# PCBA-2075-01.net
KiCad netlist of a schematic drawn in Altium Designer
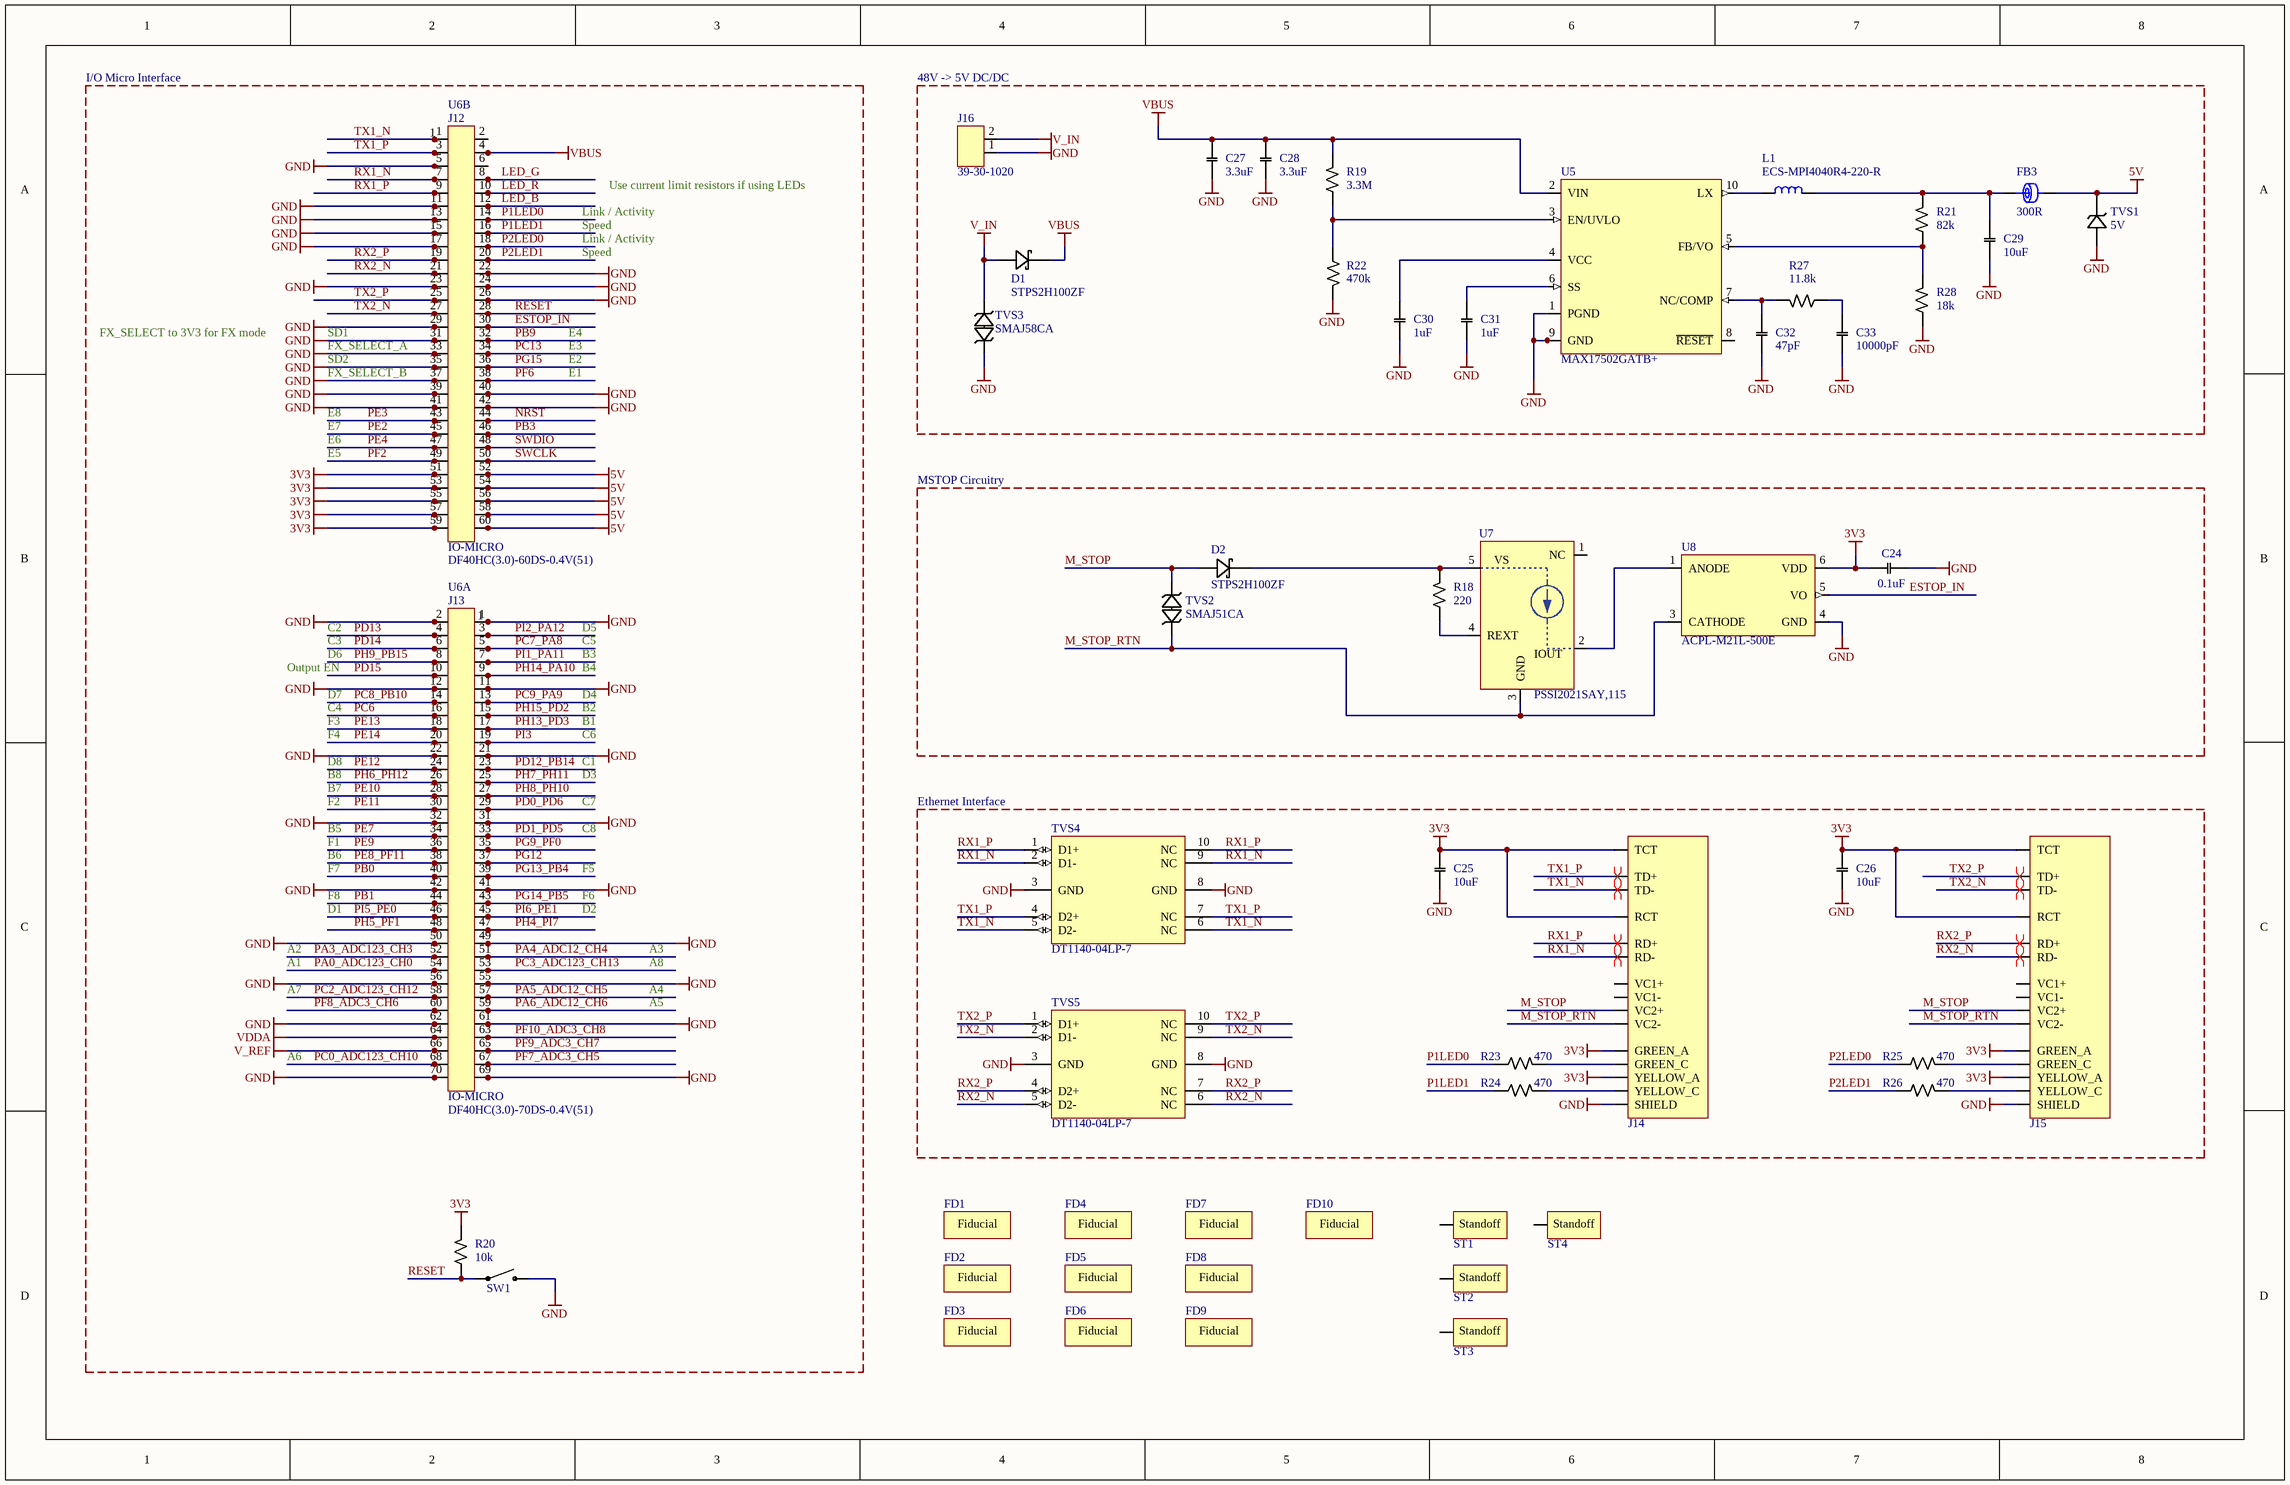
[diagram p0: PCBA-2075-01.SchDoc]

(export (version "E")
  (design (tool "Eeschema 10.0.6"))
  (components
    (comp (ref "C24")
      (value "C-0.1uf-X7R-25V-10%-0402")
      (footprint "C0402")
      (description "Capacitor Ceramic 0.1uF 25V X7R 10% SMD 0402")
      (fields (field (name "TOLERANCE") "10%") (field (name "CAPACITANCE") "0.1uF"))
      (libsource (lib "Hebi Robotics") (part "Capacitor"))
    )
    (comp (ref "C25")
      (value "C-10uf-X5R-25V-10%-0805")
      (footprint "C0805")
      (description "Capacitor Ceramic 10uF 25V X5R 10% SMD 0805")
      (fields (field (name "TOLERANCE") "10%") (field (name "CAPACITANCE") "10uF"))
      (libsource (lib "Hebi Robotics") (part "Capacitor"))
    )
    (comp (ref "C26")
      (value "C-10uf-X5R-25V-10%-0805")
      (footprint "C0805")
      (description "Capacitor Ceramic 10uF 25V X5R 10% SMD 0805")
      (fields (field (name "TOLERANCE") "10%") (field (name "CAPACITANCE") "10uF"))
      (libsource (lib "Hebi Robotics") (part "Capacitor"))
    )
    (comp (ref "C27")
      (value "C-3.3uf-X7S-100V-10%-1206")
      (footprint "C1206")
      (description "Capacitor Ceramic 3.3uF 100V X7S 10% SMD 1206")
      (fields (field (name "TOLERANCE") "±10%") (field (name "CAPACITANCE") "3.3uF"))
      (libsource (lib "Hebi Robotics") (part "Capacitor"))
    )
    (comp (ref "C28")
      (value "C-3.3uf-X7S-100V-10%-1206")
      (footprint "C1206")
      (description "Capacitor Ceramic 3.3uF 100V X7S 10% SMD 1206")
      (fields (field (name "TOLERANCE") "±10%") (field (name "CAPACITANCE") "3.3uF"))
      (libsource (lib "Hebi Robotics") (part "Capacitor"))
    )
    (comp (ref "C29")
      (value "C-10uf-X5R-16V-10%-0603")
      (footprint "C0603")
      (description "Capacitor Ceramic 10uF 16V X5R 10% SMD 0603")
      (fields (field (name "TOLERANCE") "10%") (field (name "CAPACITANCE") "10uF"))
      (libsource (lib "Hebi Robotics") (part "Capacitor"))
    )
    (comp (ref "C30")
      (value "C-1uf-X5R-25V-10%-0402")
      (footprint "C0402")
      (description "Capacitor Ceramic 1uF 25V X5R 10% SMD 0402")
      (fields (field (name "TOLERANCE") "±10%") (field (name "CAPACITANCE") "1uF"))
      (libsource (lib "Hebi Robotics") (part "Capacitor"))
    )
    (comp (ref "C31")
      (value "C-1uf-X5R-25V-10%-0402")
      (footprint "C0402")
      (description "Capacitor Ceramic 1uF 25V X5R 10% SMD 0402")
      (fields (field (name "TOLERANCE") "±10%") (field (name "CAPACITANCE") "1uF"))
      (libsource (lib "Hebi Robotics") (part "Capacitor"))
    )
    (comp (ref "C32")
      (value "C-47pf-C0G-NP0-50V-5%-0402")
      (footprint "C0402")
      (description "Capacitor Ceramic 47pF 50V C0G, NP0 5% SMD 0402")
      (fields (field (name "CAPACITANCE") "47pF") (field (name "TOLERANCE") "±5%"))
      (libsource (lib "Hebi Robotics") (part "Capacitor"))
    )
    (comp (ref "C33")
      (value "C-10000pf-X7R-50V-10%-0402")
      (footprint "C0402")
      (description "Capacitor Ceramic 10000pF 50V X7R 10% SMD 0402")
      (fields (field (name "TOLERANCE") "10%") (field (name "CAPACITANCE") "10000pF"))
      (libsource (lib "Hebi Robotics") (part "Capacitor"))
    )
    (comp (ref "D1")
      (value "STPS2H100ZF")
      (footprint "SOD123F_ST")
      (description "DIODE SCHOTTKY 100V 2A SOD123F")
      (libsource (lib "Hebi Robotics") (part "SCHOTTKY"))
    )
    (comp (ref "D2")
      (value "STPS2H100ZF")
      (footprint "SOD123F_ST")
      (description "DIODE SCHOTTKY 100V 2A SOD123F")
      (libsource (lib "Hebi Robotics") (part "SCHOTTKY"))
    )
    (comp (ref "FB3")
      (value "MI0603L301R-10")
      (footprint "FB0603")
      (description "FERRITE BEAD 300 OHM 0603 2A")
      (fields (field (name "IMPEDANCE") "300R"))
      (libsource (lib "Hebi Robotics") (part "FB"))
    )
    (comp (ref "FD1")
      (value "Fiducial")
      (footprint "New footprint 1")
      (description "Fiducial with Overlay")
      (libsource (lib "Hebi Robotics") (part "FIDUCIAL"))
    )
    (comp (ref "FD2")
      (value "Fiducial")
      (footprint "New footprint 1")
      (description "Fiducial with Overlay")
      (libsource (lib "Hebi Robotics") (part "FIDUCIAL"))
    )
    (comp (ref "FD3")
      (value "Fiducial")
      (footprint "New footprint 1")
      (description "Fiducial with Overlay")
      (libsource (lib "Hebi Robotics") (part "FIDUCIAL"))
    )
    (comp (ref "FD4")
      (value "Fiducial")
      (footprint "New footprint 1")
      (description "Fiducial with Overlay")
      (libsource (lib "Hebi Robotics") (part "FIDUCIAL"))
    )
    (comp (ref "FD5")
      (value "Fiducial No Overlay")
      (footprint "New footprint 1")
      (description "Fiducial without Overlay")
      (libsource (lib "Hebi Robotics") (part "FIDUCIAL"))
    )
    (comp (ref "FD6")
      (value "Fiducial No Overlay")
      (footprint "New footprint 1")
      (description "Fiducial without Overlay")
      (libsource (lib "Hebi Robotics") (part "FIDUCIAL"))
    )
    (comp (ref "FD7")
      (value "Fiducial No Overlay")
      (footprint "New footprint 1")
      (description "Fiducial without Overlay")
      (libsource (lib "Hebi Robotics") (part "FIDUCIAL"))
    )
    (comp (ref "FD8")
      (value "Fiducial No Overlay")
      (footprint "New footprint 1")
      (description "Fiducial without Overlay")
      (libsource (lib "Hebi Robotics") (part "FIDUCIAL"))
    )
    (comp (ref "FD9")
      (value "Fiducial No Overlay")
      (footprint "New footprint 1")
      (description "Fiducial without Overlay")
      (libsource (lib "Hebi Robotics") (part "FIDUCIAL"))
    )
    (comp (ref "FD10")
      (value "Fiducial No Overlay")
      (footprint "New footprint 1")
      (description "Fiducial without Overlay")
      (libsource (lib "Hebi Robotics") (part "FIDUCIAL"))
    )
    (comp (ref "J12")
      (value "DF40HC(3.0)-60DS-0.4V(51)")
      (footprint "DF40HC(3.0)-60DS-0.4V(51)")
      (description "CONN RCPT 60POS 0.4MM SMD GOLD")
      (libsource (lib "Hebi Robotics") (part "CONN_2_ROW_060_POS"))
    )
    (comp (ref "J13")
      (value "DF40HC(3.0)-70DS-0.4V(51)")
      (footprint "DF40HC(3.0)-70DS-0.4V(51)")
      (description "CONN RCPT 70POS 0.4MM SMD GOLD")
      (fields (field (name "MANUFACTURER") "Hirose"))
      (libsource (lib "Hebi Robotics") (part "CONN_2_ROW_070_POS"))
    )
    (comp (ref "J14")
      (value "ARJM11C7-114-BA-EW2")
      (footprint "ARJM11C7-114-BA-EW2-Footprint-1")
      (description "1 Port RJ45 Magjack Connector Through Hole 10/100 Base-T, AutoMDIX, Power over Ethernet (PoE)")
      (libsource (lib "Hebi Robotics") (part "ARJM11C7-114-BA-EW2"))
    )
    (comp (ref "J15")
      (value "ARJM11C7-114-BA-EW2")
      (footprint "ARJM11C7-114-BA-EW2-Footprint-1")
      (description "1 Port RJ45 Magjack Connector Through Hole 10/100 Base-T, AutoMDIX, Power over Ethernet (PoE)")
      (libsource (lib "Hebi Robotics") (part "ARJM11C7-114-BA-EW2"))
    )
    (comp (ref "J16")
      (value "39-30-1020")
      (footprint "39-30-1020")
      (description "CONN HEADER 2POS 4.2MM R/A TIN")
      (fields (field (name "MANUFACTURER") "Molex Inc"))
      (libsource (lib "Hebi Robotics") (part "CONN_1_ROW_002_POS"))
    )
    (comp (ref "L1")
      (value "ECS-MPI4040R4-220-R")
      (footprint "MPI4040R4")
      (description "FIXED IND 22UH 1.3A 316 MOHM SMD")
      (fields (field (name "TOLERANCE") "±20%"))
      (libsource (lib "Hebi Robotics") (part "Inductor"))
    )
    (comp (ref "R18")
      (value "R-220-1%-0.25w-0603")
      (footprint "R0603")
      (description "Resistor 0603 220 Ohm 1% 1-4 Watt")
      (fields (field (name "POWER") "0.25W, 1/4W") (field (name "RESISTANCE") "220"))
      (libsource (lib "Hebi Robotics") (part "Resistor"))
    )
    (comp (ref "R19")
      (value "R-3.3m-1%-0.063w-0402")
      (footprint "R0402")
      (description "Resistor 0402 3.3m Ohm 1% 1-16 Watt")
      (fields (field (name "POWER") "0.063W, 1/16W") (field (name "RESISTANCE") "3.3M"))
      (libsource (lib "Hebi Robotics") (part "Resistor"))
    )
    (comp (ref "R20")
      (value "R-10k-1%-0.063w-0402")
      (footprint "R0402")
      (description "Resistor 0402 10k Ohm 1% 1-16 Watt")
      (fields
        (field (name "POWER") "0.063W, 1/16W")
        (field (name "RESISTANCE") "10k")
        (field (name "TOLERANCE") "1%")
      )
      (libsource (lib "Hebi Robotics") (part "Resistor"))
    )
    (comp (ref "R21")
      (value "R-82k-1%-0.063w-0402")
      (footprint "R0402")
      (description "Resistor 0402 82k Ohm 1% 1-16 Watt")
      (fields (field (name "POWER") "0.063W, 1/16W") (field (name "RESISTANCE") "82k"))
      (libsource (lib "Hebi Robotics") (part "Resistor"))
    )
    (comp (ref "R22")
      (value "R-470k-1%-0.063w-0402")
      (footprint "R0402")
      (description "Resistor 0402 470k Ohm 1% 1-16 Watt")
      (fields
        (field (name "POWER") "0.063W, 1/16W")
        (field (name "RESISTANCE") "470k")
        (field (name "TOLERANCE") "1%")
      )
      (libsource (lib "Hebi Robotics") (part "Resistor"))
    )
    (comp (ref "R23")
      (value "R-470-1%-0.063w-0402")
      (footprint "R0402")
      (description "Resistor 0402 470 Ohm 1% 1-16 Watt")
      (fields
        (field (name "POWER") "0.063W, 1/16W")
        (field (name "RESISTANCE") "470")
        (field (name "TOLERANCE") "1%")
      )
      (libsource (lib "Hebi Robotics") (part "Resistor"))
    )
    (comp (ref "R24")
      (value "R-470-1%-0.063w-0402")
      (footprint "R0402")
      (description "Resistor 0402 470 Ohm 1% 1-16 Watt")
      (fields
        (field (name "POWER") "0.063W, 1/16W")
        (field (name "RESISTANCE") "470")
        (field (name "TOLERANCE") "1%")
      )
      (libsource (lib "Hebi Robotics") (part "Resistor"))
    )
    (comp (ref "R25")
      (value "R-470-1%-0.063w-0402")
      (footprint "R0402")
      (description "Resistor 0402 470 Ohm 1% 1-16 Watt")
      (fields
        (field (name "POWER") "0.063W, 1/16W")
        (field (name "RESISTANCE") "470")
        (field (name "TOLERANCE") "1%")
      )
      (libsource (lib "Hebi Robotics") (part "Resistor"))
    )
    (comp (ref "R26")
      (value "R-470-1%-0.063w-0402")
      (footprint "R0402")
      (description "Resistor 0402 470 Ohm 1% 1-16 Watt")
      (fields
        (field (name "POWER") "0.063W, 1/16W")
        (field (name "RESISTANCE") "470")
        (field (name "TOLERANCE") "1%")
      )
      (libsource (lib "Hebi Robotics") (part "Resistor"))
    )
    (comp (ref "R27")
      (value "R-11.8k-1%-0.063w-0402")
      (footprint "R0402")
      (description "Resistor 0402 11.8k Ohm 1% 1-16 Watt")
      (fields (field (name "POWER") "0.063W, 1/16W") (field (name "RESISTANCE") "11.8k"))
      (libsource (lib "Hebi Robotics") (part "Resistor"))
    )
    (comp (ref "R28")
      (value "R-18k-1%-0.063w-0402")
      (footprint "R0402")
      (description "Resistor 0402 18k Ohm 1% 1-16 Watt")
      (fields
        (field (name "TOLERANCE") "1%")
        (field (name "POWER") "0.063W, 1/16W")
        (field (name "RESISTANCE") "18k")
      )
      (libsource (lib "Hebi Robotics") (part "Resistor"))
    )
    (comp (ref "ST1")
      (value "9774030960R")
      (footprint "9774030960R")
      (description "ROUND SPACER M3.3 STEEL 3MM")
      (fields (field (name "MANUFACTURER") "Wurth Electronics Inc"))
      (libsource (lib "Hebi Robotics") (part "STANDOFF_PIN"))
    )
    (comp (ref "ST2")
      (value "9774030960R")
      (footprint "9774030960R")
      (description "ROUND SPACER M3.3 STEEL 3MM")
      (fields (field (name "MANUFACTURER") "Wurth Electronics Inc"))
      (libsource (lib "Hebi Robotics") (part "STANDOFF_PIN"))
    )
    (comp (ref "ST3")
      (value "9774030960R")
      (footprint "9774030960R")
      (description "ROUND SPACER M3.3 STEEL 3MM")
      (fields (field (name "MANUFACTURER") "Wurth Electronics Inc"))
      (libsource (lib "Hebi Robotics") (part "STANDOFF_PIN"))
    )
    (comp (ref "ST4")
      (value "9774030960R")
      (footprint "9774030960R")
      (description "ROUND SPACER M3.3 STEEL 3MM")
      (fields (field (name "MANUFACTURER") "Wurth Electronics Inc"))
      (libsource (lib "Hebi Robotics") (part "STANDOFF_PIN"))
    )
    (comp (ref "SW1")
      (value "222ADVBA")
      (footprint "222ADVBA")
      (description "Tactile Switch SPST-NO Top Actuated Through Hole")
      (fields (field (name "MANUFACTURER") "CTS"))
      (libsource (lib "Hebi Robotics") (part "SPST_NO"))
    )
    (comp (ref "TVS1")
      (value "PTVS5V0S1UR,115")
      (footprint "SOD-123W_NXP")
      (description "TVS DIODE 5VWM 9.2VC SOD123W")
      (fields (field (name "VOLTAGE - REVERSE STANDOFF (TYP)") "5V"))
      (libsource (lib "Hebi Robotics") (part "TVS"))
    )
    (comp (ref "TVS2")
      (value "SMAJ51CA")
      (footprint "SMA_BI_BOURNS")
      (description "TVS DIODE 51VWM 82.4VC DO214AC")
      (libsource (lib "Hebi Robotics") (part "TVS_BI"))
    )
    (comp (ref "TVS3")
      (value "SMAJ58CA")
      (footprint "SMA_BI_BOURNS")
      (description "TVS DIODE 58VWM 93.6VC SMA")
      (libsource (lib "Hebi Robotics") (part "TVS_BI"))
    )
    (comp (ref "TVS4")
      (value "DT1140-04LP-7")
      (footprint "USON10_TI")
      (description "TVS DIODE 5.5V 10V U-DFN2510-10")
      (libsource (lib "Hebi Robotics") (part "10-UFDFN-TVS"))
    )
    (comp (ref "TVS5")
      (value "DT1140-04LP-7")
      (footprint "USON10_TI")
      (description "TVS DIODE 5.5V 10V U-DFN2510-10")
      (libsource (lib "Hebi Robotics") (part "10-UFDFN-TVS"))
    )
    (comp (ref "U5")
      (value "MAX17502GATB+")
      (footprint "10_TDFN_MAXIM")
      (description "Switching Voltage Regulators 60V 1A 600kHz Synch Step-Down Regulator")
      (libsource (lib "Hebi Robotics") (part "MAX17502E_F_G"))
    )
    (comp (ref "U6")
      (value "IO-MICRO")
      (footprint "IO-MICRO-Footprint-1")
      (description "IO Micro Composite Component")
      (libsource (lib "") (part "IO-MICRO-Symbol-1_1"))
    )
    (comp (ref "U7")
      (value "PSSI2021SAY,115")
      (footprint "PSSI2021SAY,115")
      (description "IC CURRENT SOURCE SOT353")
      (libsource (lib "Hebi Robotics") (part "PSSI2021SAY,115"))
    )
    (comp (ref "U8")
      (value "ACPL-M21L-500E")
      (footprint "SOT125P700X260-5N")
      (description "OPTOISO 3.75KV PUSH PULL 5SO")
      (libsource (lib "Hebi Robotics") (part "Symbol"))
    )
  )
  (nets
    (net (code "1") (name "/ESTOP_IN") (class "Default")
      (node (ref "J12") (pin "30") (pinfunction "30_30") (pintype "passive"))
      (node (ref "U6") (pin "B30") (pinfunction "B30_B30") (pintype "passive"))
      (node (ref "U8") (pin "5") (pinfunction "VO_5") (pintype "output"))
    )
    (net (code "2") (name "/LED_B") (class "Default")
      (node (ref "J12") (pin "12") (pinfunction "12_12") (pintype "passive"))
      (node (ref "U6") (pin "B12") (pinfunction "B12_B12") (pintype "passive"))
    )
    (net (code "3") (name "/LED_G") (class "Default")
      (node (ref "J12") (pin "8") (pinfunction "8_8") (pintype "passive"))
      (node (ref "U6") (pin "B8") (pinfunction "B8_B8") (pintype "passive"))
    )
    (net (code "4") (name "/LED_R") (class "Default")
      (node (ref "J12") (pin "10") (pinfunction "10_10") (pintype "passive"))
      (node (ref "U6") (pin "B10") (pinfunction "B10_B10") (pintype "passive"))
    )
    (net (code "5") (name "/M_STOP") (class "Default")
      (node (ref "D2") (pin "A") (pinfunction "A_A") (pintype "passive"))
      (node (ref "J14") (pin "6") (pinfunction "VC2+_6") (pintype "passive"))
      (node (ref "J15") (pin "6") (pinfunction "VC2+_6") (pintype "passive"))
      (node (ref "TVS2") (pin "C") (pinfunction "C_C") (pintype "passive"))
    )
    (net (code "6") (name "/M_STOP_RTN") (class "Default")
      (node (ref "J14") (pin "1") (pinfunction "VC2-_1") (pintype "passive"))
      (node (ref "J15") (pin "1") (pinfunction "VC2-_1") (pintype "passive"))
      (node (ref "TVS2") (pin "A") (pinfunction "A_A") (pintype "passive"))
      (node (ref "U7") (pin "3") (pinfunction "GND_3") (pintype "passive"))
      (node (ref "U8") (pin "3") (pinfunction "CATHODE_3") (pintype "passive"))
    )
    (net (code "7") (name "/NRST") (class "Default")
      (node (ref "J12") (pin "44") (pinfunction "44_44") (pintype "passive"))
      (node (ref "U6") (pin "B44") (pinfunction "B44_B44") (pintype "passive"))
    )
    (net (code "8") (name "/P1LED0") (class "Default")
      (node (ref "J12") (pin "14") (pinfunction "14_14") (pintype "passive"))
      (node (ref "R23") (pin "1") (pinfunction "1_1") (pintype "passive"))
      (node (ref "U6") (pin "B14") (pinfunction "B14_B14") (pintype "passive"))
    )
    (net (code "9") (name "/P1LED1") (class "Default")
      (node (ref "J12") (pin "16") (pinfunction "16_16") (pintype "passive"))
      (node (ref "R24") (pin "1") (pinfunction "1_1") (pintype "passive"))
      (node (ref "U6") (pin "B16") (pinfunction "B16_B16") (pintype "passive"))
    )
    (net (code "10") (name "/P2LED0") (class "Default")
      (node (ref "J12") (pin "18") (pinfunction "18_18") (pintype "passive"))
      (node (ref "R25") (pin "1") (pinfunction "1_1") (pintype "passive"))
      (node (ref "U6") (pin "B18") (pinfunction "B18_B18") (pintype "passive"))
    )
    (net (code "11") (name "/P2LED1") (class "Default")
      (node (ref "J12") (pin "20") (pinfunction "20_20") (pintype "passive"))
      (node (ref "R26") (pin "1") (pinfunction "1_1") (pintype "passive"))
      (node (ref "U6") (pin "B20") (pinfunction "B20_B20") (pintype "passive"))
    )
    (net (code "12") (name "/PA0_ADC123_CH0") (class "Default")
      (node (ref "J13") (pin "54") (pinfunction "54_54") (pintype "passive"))
      (node (ref "U6") (pin "A54") (pinfunction "A54_A54") (pintype "passive"))
    )
    (net (code "13") (name "/PA3_ADC123_CH3") (class "Default")
      (node (ref "J13") (pin "52") (pinfunction "52_52") (pintype "passive"))
      (node (ref "U6") (pin "A52") (pinfunction "A52_A52") (pintype "passive"))
    )
    (net (code "14") (name "/PA4_ADC12_CH4") (class "Default")
      (node (ref "J13") (pin "51") (pinfunction "51_51") (pintype "passive"))
      (node (ref "U6") (pin "A51") (pinfunction "A51_A51") (pintype "passive"))
    )
    (net (code "15") (name "/PA5_ADC12_CH5") (class "Default")
      (node (ref "J13") (pin "57") (pinfunction "57_57") (pintype "passive"))
      (node (ref "U6") (pin "A57") (pinfunction "A57_A57") (pintype "passive"))
    )
    (net (code "16") (name "/PA6_ADC12_CH6") (class "Default")
      (node (ref "J13") (pin "59") (pinfunction "59_59") (pintype "passive"))
      (node (ref "U6") (pin "A59") (pinfunction "A59_A59") (pintype "passive"))
    )
    (net (code "17") (name "/PB0") (class "Default")
      (node (ref "J13") (pin "40") (pinfunction "40_40") (pintype "passive"))
      (node (ref "U6") (pin "A40") (pinfunction "A40_A40") (pintype "passive"))
    )
    (net (code "18") (name "/PB1") (class "Default")
      (node (ref "J13") (pin "44") (pinfunction "44_44") (pintype "passive"))
      (node (ref "U6") (pin "A44") (pinfunction "A44_A44") (pintype "passive"))
    )
    (net (code "19") (name "/PB3") (class "Default")
      (node (ref "J12") (pin "46") (pinfunction "46_46") (pintype "passive"))
      (node (ref "U6") (pin "B46") (pinfunction "B46_B46") (pintype "passive"))
    )
    (net (code "20") (name "/PB9") (class "Default")
      (node (ref "J12") (pin "32") (pinfunction "32_32") (pintype "passive"))
      (node (ref "U6") (pin "B32") (pinfunction "B32_B32") (pintype "passive"))
    )
    (net (code "21") (name "/PC0_ADC123_CH10") (class "Default")
      (node (ref "J13") (pin "68") (pinfunction "68_68") (pintype "passive"))
      (node (ref "U6") (pin "A68") (pinfunction "A68_A68") (pintype "passive"))
    )
    (net (code "22") (name "/PC2_ADC123_CH12") (class "Default")
      (node (ref "J13") (pin "58") (pinfunction "58_58") (pintype "passive"))
      (node (ref "U6") (pin "A58") (pinfunction "A58_A58") (pintype "passive"))
    )
    (net (code "23") (name "/PC3_ADC123_CH13") (class "Default")
      (node (ref "J13") (pin "53") (pinfunction "53_53") (pintype "passive"))
      (node (ref "U6") (pin "A53") (pinfunction "A53_A53") (pintype "passive"))
    )
    (net (code "24") (name "/PC6") (class "Default")
      (node (ref "J13") (pin "16") (pinfunction "16_16") (pintype "passive"))
      (node (ref "U6") (pin "A16") (pinfunction "A16_A16") (pintype "passive"))
    )
    (net (code "25") (name "/PC7_PA8") (class "Default")
      (node (ref "J13") (pin "5") (pinfunction "5_5") (pintype "passive"))
      (node (ref "U6") (pin "A5") (pinfunction "A5_A5") (pintype "passive"))
    )
    (net (code "26") (name "/PC8_PB10") (class "Default")
      (node (ref "J13") (pin "14") (pinfunction "14_14") (pintype "passive"))
      (node (ref "U6") (pin "A14") (pinfunction "A14_A14") (pintype "passive"))
    )
    (net (code "27") (name "/PC9_PA9") (class "Default")
      (node (ref "J13") (pin "13") (pinfunction "13_13") (pintype "passive"))
      (node (ref "U6") (pin "A13") (pinfunction "A13_A13") (pintype "passive"))
    )
    (net (code "28") (name "/PC13") (class "Default")
      (node (ref "J12") (pin "34") (pinfunction "34_34") (pintype "passive"))
      (node (ref "U6") (pin "B34") (pinfunction "B34_B34") (pintype "passive"))
    )
    (net (code "29") (name "/PD0_PD6") (class "Default")
      (node (ref "J13") (pin "29") (pinfunction "29_29") (pintype "passive"))
      (node (ref "U6") (pin "A29") (pinfunction "A29_A29") (pintype "passive"))
    )
    (net (code "30") (name "/PD1_PD5") (class "Default")
      (node (ref "J13") (pin "33") (pinfunction "33_33") (pintype "passive"))
      (node (ref "U6") (pin "A33") (pinfunction "A33_A33") (pintype "passive"))
    )
    (net (code "31") (name "/PD12_PB14") (class "Default")
      (node (ref "J13") (pin "23") (pinfunction "23_23") (pintype "passive"))
      (node (ref "U6") (pin "A23") (pinfunction "A23_A23") (pintype "passive"))
    )
    (net (code "32") (name "/PD13") (class "Default")
      (node (ref "J13") (pin "4") (pinfunction "4_4") (pintype "passive"))
      (node (ref "U6") (pin "A4") (pinfunction "A4_A4") (pintype "passive"))
    )
    (net (code "33") (name "/PD14") (class "Default")
      (node (ref "J13") (pin "6") (pinfunction "6_6") (pintype "passive"))
      (node (ref "U6") (pin "A6") (pinfunction "A6_A6") (pintype "passive"))
    )
    (net (code "34") (name "/PD15") (class "Default")
      (node (ref "J13") (pin "10") (pinfunction "10_10") (pintype "passive"))
      (node (ref "U6") (pin "A10") (pinfunction "A10_A10") (pintype "passive"))
    )
    (net (code "35") (name "/PE2") (class "Default")
      (node (ref "J12") (pin "45") (pinfunction "45_45") (pintype "passive"))
      (node (ref "U6") (pin "B45") (pinfunction "B45_B45") (pintype "passive"))
    )
    (net (code "36") (name "/PE3") (class "Default")
      (node (ref "J12") (pin "43") (pinfunction "43_43") (pintype "passive"))
      (node (ref "U6") (pin "B43") (pinfunction "B43_B43") (pintype "passive"))
    )
    (net (code "37") (name "/PE4") (class "Default")
      (node (ref "J12") (pin "47") (pinfunction "47_47") (pintype "passive"))
      (node (ref "U6") (pin "B47") (pinfunction "B47_B47") (pintype "passive"))
    )
    (net (code "38") (name "/PE7") (class "Default")
      (node (ref "J13") (pin "34") (pinfunction "34_34") (pintype "passive"))
      (node (ref "U6") (pin "A34") (pinfunction "A34_A34") (pintype "passive"))
    )
    (net (code "39") (name "/PE8_PF11") (class "Default")
      (node (ref "J13") (pin "38") (pinfunction "38_38") (pintype "passive"))
      (node (ref "U6") (pin "A38") (pinfunction "A38_A38") (pintype "passive"))
    )
    (net (code "40") (name "/PE9") (class "Default")
      (node (ref "J13") (pin "36") (pinfunction "36_36") (pintype "passive"))
      (node (ref "U6") (pin "A36") (pinfunction "A36_A36") (pintype "passive"))
    )
    (net (code "41") (name "/PE10") (class "Default")
      (node (ref "J13") (pin "28") (pinfunction "28_28") (pintype "passive"))
      (node (ref "U6") (pin "A28") (pinfunction "A28_A28") (pintype "passive"))
    )
    (net (code "42") (name "/PE11") (class "Default")
      (node (ref "J13") (pin "30") (pinfunction "30_30") (pintype "passive"))
      (node (ref "U6") (pin "A30") (pinfunction "A30_A30") (pintype "passive"))
    )
    (net (code "43") (name "/PE12") (class "Default")
      (node (ref "J13") (pin "24") (pinfunction "24_24") (pintype "passive"))
      (node (ref "U6") (pin "A24") (pinfunction "A24_A24") (pintype "passive"))
    )
    (net (code "44") (name "/PE13") (class "Default")
      (node (ref "J13") (pin "18") (pinfunction "18_18") (pintype "passive"))
      (node (ref "U6") (pin "A18") (pinfunction "A18_A18") (pintype "passive"))
    )
    (net (code "45") (name "/PE14") (class "Default")
      (node (ref "J13") (pin "20") (pinfunction "20_20") (pintype "passive"))
      (node (ref "U6") (pin "A20") (pinfunction "A20_A20") (pintype "passive"))
    )
    (net (code "46") (name "/PF2") (class "Default")
      (node (ref "J12") (pin "49") (pinfunction "49_49") (pintype "passive"))
      (node (ref "U6") (pin "B49") (pinfunction "B49_B49") (pintype "passive"))
    )
    (net (code "47") (name "/PF6") (class "Default")
      (node (ref "J12") (pin "38") (pinfunction "38_38") (pintype "passive"))
      (node (ref "U6") (pin "B38") (pinfunction "B38_B38") (pintype "passive"))
    )
    (net (code "48") (name "/PF7_ADC3_CH5") (class "Default")
      (node (ref "J13") (pin "67") (pinfunction "67_67") (pintype "passive"))
      (node (ref "U6") (pin "A67") (pinfunction "A67_A67") (pintype "passive"))
    )
    (net (code "49") (name "/PF8_ADC3_CH6") (class "Default")
      (node (ref "J13") (pin "60") (pinfunction "60_60") (pintype "passive"))
      (node (ref "U6") (pin "A60") (pinfunction "A60_A60") (pintype "passive"))
    )
    (net (code "50") (name "/PF9_ADC3_CH7") (class "Default")
      (node (ref "J13") (pin "65") (pinfunction "65_65") (pintype "passive"))
      (node (ref "U6") (pin "A65") (pinfunction "A65_A65") (pintype "passive"))
    )
    (net (code "51") (name "/PF10_ADC3_CH8") (class "Default")
      (node (ref "J13") (pin "63") (pinfunction "63_63") (pintype "passive"))
      (node (ref "U6") (pin "A63") (pinfunction "A63_A63") (pintype "passive"))
    )
    (net (code "52") (name "/PG9_PF0") (class "Default")
      (node (ref "J13") (pin "35") (pinfunction "35_35") (pintype "passive"))
      (node (ref "U6") (pin "A35") (pinfunction "A35_A35") (pintype "passive"))
    )
    (net (code "53") (name "/PG12") (class "Default")
      (node (ref "J13") (pin "37") (pinfunction "37_37") (pintype "passive"))
      (node (ref "U6") (pin "A37") (pinfunction "A37_A37") (pintype "passive"))
    )
    (net (code "54") (name "/PG13_PB4") (class "Default")
      (node (ref "J13") (pin "39") (pinfunction "39_39") (pintype "passive"))
      (node (ref "U6") (pin "A39") (pinfunction "A39_A39") (pintype "passive"))
    )
    (net (code "55") (name "/PG14_PB5") (class "Default")
      (node (ref "J13") (pin "43") (pinfunction "43_43") (pintype "passive"))
      (node (ref "U6") (pin "A43") (pinfunction "A43_A43") (pintype "passive"))
    )
    (net (code "56") (name "/PG15") (class "Default")
      (node (ref "J12") (pin "36") (pinfunction "36_36") (pintype "passive"))
      (node (ref "U6") (pin "B36") (pinfunction "B36_B36") (pintype "passive"))
    )
    (net (code "57") (name "/PH4_PI7") (class "Default")
      (node (ref "J13") (pin "47") (pinfunction "47_47") (pintype "passive"))
      (node (ref "U6") (pin "A47") (pinfunction "A47_A47") (pintype "passive"))
    )
    (net (code "58") (name "/PH5_PF1") (class "Default")
      (node (ref "J13") (pin "48") (pinfunction "48_48") (pintype "passive"))
      (node (ref "U6") (pin "A48") (pinfunction "A48_A48") (pintype "passive"))
    )
    (net (code "59") (name "/PH6_PH12") (class "Default")
      (node (ref "J13") (pin "26") (pinfunction "26_26") (pintype "passive"))
      (node (ref "U6") (pin "A26") (pinfunction "A26_A26") (pintype "passive"))
    )
    (net (code "60") (name "/PH7_PH11") (class "Default")
      (node (ref "J13") (pin "25") (pinfunction "25_25") (pintype "passive"))
      (node (ref "U6") (pin "A25") (pinfunction "A25_A25") (pintype "passive"))
    )
    (net (code "61") (name "/PH8_PH10") (class "Default")
      (node (ref "J13") (pin "27") (pinfunction "27_27") (pintype "passive"))
      (node (ref "U6") (pin "A27") (pinfunction "A27_A27") (pintype "passive"))
    )
    (net (code "62") (name "/PH9_PB15") (class "Default")
      (node (ref "J13") (pin "8") (pinfunction "8_8") (pintype "passive"))
      (node (ref "U6") (pin "A8") (pinfunction "A8_A8") (pintype "passive"))
    )
    (net (code "63") (name "/PH13_PD3") (class "Default")
      (node (ref "J13") (pin "17") (pinfunction "17_17") (pintype "passive"))
      (node (ref "U6") (pin "A17") (pinfunction "A17_A17") (pintype "passive"))
    )
    (net (code "64") (name "/PH14_PA10") (class "Default")
      (node (ref "J13") (pin "9") (pinfunction "9_9") (pintype "passive"))
      (node (ref "U6") (pin "A9") (pinfunction "A9_A9") (pintype "passive"))
    )
    (net (code "65") (name "/PH15_PD2") (class "Default")
      (node (ref "J13") (pin "15") (pinfunction "15_15") (pintype "passive"))
      (node (ref "U6") (pin "A15") (pinfunction "A15_A15") (pintype "passive"))
    )
    (net (code "66") (name "/PI1_PA11") (class "Default")
      (node (ref "J13") (pin "7") (pinfunction "7_7") (pintype "passive"))
      (node (ref "U6") (pin "A7") (pinfunction "A7_A7") (pintype "passive"))
    )
    (net (code "67") (name "/PI2_PA12") (class "Default")
      (node (ref "J13") (pin "3") (pinfunction "3_3") (pintype "passive"))
      (node (ref "U6") (pin "A3") (pinfunction "A3_A3") (pintype "passive"))
    )
    (net (code "68") (name "/PI3") (class "Default")
      (node (ref "J13") (pin "19") (pinfunction "19_19") (pintype "passive"))
      (node (ref "U6") (pin "A19") (pinfunction "A19_A19") (pintype "passive"))
    )
    (net (code "69") (name "/PI5_PE0") (class "Default")
      (node (ref "J13") (pin "46") (pinfunction "46_46") (pintype "passive"))
      (node (ref "U6") (pin "A46") (pinfunction "A46_A46") (pintype "passive"))
    )
    (net (code "70") (name "/PI6_PE1") (class "Default")
      (node (ref "J13") (pin "45") (pinfunction "45_45") (pintype "passive"))
      (node (ref "U6") (pin "A45") (pinfunction "A45_A45") (pintype "passive"))
    )
    (net (code "71") (name "/RESET") (class "Default")
      (node (ref "J12") (pin "28") (pinfunction "28_28") (pintype "passive"))
      (node (ref "R20") (pin "1") (pinfunction "1_1") (pintype "passive"))
      (node (ref "SW1") (pin "1") (pinfunction "1_1") (pintype "passive"))
      (node (ref "U6") (pin "B28") (pinfunction "B28_B28") (pintype "passive"))
    )
    (net (code "72") (name "/RX1_N") (class "Default")
      (node (ref "J12") (pin "7") (pinfunction "7_7") (pintype "passive"))
      (node (ref "J14") (pin "3") (pinfunction "RD-_3") (pintype "passive"))
      (node (ref "TVS4") (pin "2") (pinfunction "D1-_2") (pintype "bidirectional"))
      (node (ref "TVS4") (pin "9") (pinfunction "NC_9") (pintype "passive"))
      (node (ref "U6") (pin "B7") (pinfunction "B7_B7") (pintype "passive"))
    )
    (net (code "73") (name "/RX1_P") (class "Default")
      (node (ref "J12") (pin "9") (pinfunction "9_9") (pintype "passive"))
      (node (ref "J14") (pin "5") (pinfunction "RD+_5") (pintype "passive"))
      (node (ref "TVS4") (pin "1") (pinfunction "D1+_1") (pintype "bidirectional"))
      (node (ref "TVS4") (pin "10") (pinfunction "NC_10") (pintype "passive"))
      (node (ref "U6") (pin "B9") (pinfunction "B9_B9") (pintype "passive"))
    )
    (net (code "74") (name "/RX2_N") (class "Default")
      (node (ref "J12") (pin "21") (pinfunction "21_21") (pintype "passive"))
      (node (ref "J15") (pin "3") (pinfunction "RD-_3") (pintype "passive"))
      (node (ref "TVS5") (pin "5") (pinfunction "D2-_5") (pintype "bidirectional"))
      (node (ref "TVS5") (pin "6") (pinfunction "NC_6") (pintype "passive"))
      (node (ref "U6") (pin "B21") (pinfunction "B21_B21") (pintype "passive"))
    )
    (net (code "75") (name "/RX2_P") (class "Default")
      (node (ref "J12") (pin "19") (pinfunction "19_19") (pintype "passive"))
      (node (ref "J15") (pin "5") (pinfunction "RD+_5") (pintype "passive"))
      (node (ref "TVS5") (pin "4") (pinfunction "D2+_4") (pintype "bidirectional"))
      (node (ref "TVS5") (pin "7") (pinfunction "NC_7") (pintype "passive"))
      (node (ref "U6") (pin "B19") (pinfunction "B19_B19") (pintype "passive"))
    )
    (net (code "76") (name "/SWCLK") (class "Default")
      (node (ref "J12") (pin "50") (pinfunction "50_50") (pintype "passive"))
      (node (ref "U6") (pin "B50") (pinfunction "B50_B50") (pintype "passive"))
    )
    (net (code "77") (name "/SWDIO") (class "Default")
      (node (ref "J12") (pin "48") (pinfunction "48_48") (pintype "passive"))
      (node (ref "U6") (pin "B48") (pinfunction "B48_B48") (pintype "passive"))
    )
    (net (code "78") (name "/TX1_N") (class "Default")
      (node (ref "J12") (pin "1") (pinfunction "1_1") (pintype "passive"))
      (node (ref "J14") (pin "8") (pinfunction "TD-_8") (pintype "passive"))
      (node (ref "TVS4") (pin "5") (pinfunction "D2-_5") (pintype "bidirectional"))
      (node (ref "TVS4") (pin "6") (pinfunction "NC_6") (pintype "passive"))
      (node (ref "U6") (pin "B1") (pinfunction "B1_B1") (pintype "passive"))
    )
    (net (code "79") (name "/TX1_P") (class "Default")
      (node (ref "J12") (pin "3") (pinfunction "3_3") (pintype "passive"))
      (node (ref "J14") (pin "10") (pinfunction "TD+_10") (pintype "passive"))
      (node (ref "TVS4") (pin "4") (pinfunction "D2+_4") (pintype "bidirectional"))
      (node (ref "TVS4") (pin "7") (pinfunction "NC_7") (pintype "passive"))
      (node (ref "U6") (pin "B3") (pinfunction "B3_B3") (pintype "passive"))
    )
    (net (code "80") (name "/TX2_N") (class "Default")
      (node (ref "J12") (pin "27") (pinfunction "27_27") (pintype "passive"))
      (node (ref "J15") (pin "8") (pinfunction "TD-_8") (pintype "passive"))
      (node (ref "TVS5") (pin "2") (pinfunction "D1-_2") (pintype "bidirectional"))
      (node (ref "TVS5") (pin "9") (pinfunction "NC_9") (pintype "passive"))
      (node (ref "U6") (pin "B27") (pinfunction "B27_B27") (pintype "passive"))
    )
    (net (code "81") (name "/TX2_P") (class "Default")
      (node (ref "J12") (pin "25") (pinfunction "25_25") (pintype "passive"))
      (node (ref "J15") (pin "10") (pinfunction "TD+_10") (pintype "passive"))
      (node (ref "TVS5") (pin "1") (pinfunction "D1+_1") (pintype "bidirectional"))
      (node (ref "TVS5") (pin "10") (pinfunction "NC_10") (pintype "passive"))
      (node (ref "U6") (pin "B25") (pinfunction "B25_B25") (pintype "passive"))
    )
    (net (code "82") (name "3V3") (class "Default")
      (node (ref "C24") (pin "1") (pinfunction "1_1") (pintype "passive"))
      (node (ref "C25") (pin "2") (pinfunction "2_2") (pintype "passive"))
      (node (ref "C26") (pin "2") (pinfunction "2_2") (pintype "passive"))
      (node (ref "J12") (pin "51") (pinfunction "51_51") (pintype "passive"))
      (node (ref "J12") (pin "53") (pinfunction "53_53") (pintype "passive"))
      (node (ref "J12") (pin "55") (pinfunction "55_55") (pintype "passive"))
      (node (ref "J12") (pin "57") (pinfunction "57_57") (pintype "passive"))
      (node (ref "J12") (pin "59") (pinfunction "59_59") (pintype "passive"))
      (node (ref "J14") (pin "4") (pinfunction "RCT_4") (pintype "passive"))
      (node (ref "J14") (pin "9") (pinfunction "TCT_9") (pintype "passive"))
      (node (ref "J14") (pin "L1") (pinfunction "GREEN_A_L1") (pintype "passive"))
      (node (ref "J14") (pin "L3") (pinfunction "YELLOW_A_L3") (pintype "passive"))
      (node (ref "J15") (pin "4") (pinfunction "RCT_4") (pintype "passive"))
      (node (ref "J15") (pin "9") (pinfunction "TCT_9") (pintype "passive"))
      (node (ref "J15") (pin "L1") (pinfunction "GREEN_A_L1") (pintype "passive"))
      (node (ref "J15") (pin "L3") (pinfunction "YELLOW_A_L3") (pintype "passive"))
      (node (ref "R20") (pin "2") (pinfunction "2_2") (pintype "passive"))
      (node (ref "U6") (pin "B51") (pinfunction "B51_B51") (pintype "passive"))
      (node (ref "U6") (pin "B53") (pinfunction "B53_B53") (pintype "passive"))
      (node (ref "U6") (pin "B55") (pinfunction "B55_B55") (pintype "passive"))
      (node (ref "U6") (pin "B57") (pinfunction "B57_B57") (pintype "passive"))
      (node (ref "U6") (pin "B59") (pinfunction "B59_B59") (pintype "passive"))
      (node (ref "U8") (pin "6") (pinfunction "VDD_6") (pintype "power_in"))
    )
    (net (code "83") (name "5V") (class "Default")
      (node (ref "FB3") (pin "2") (pinfunction "2_2") (pintype "passive"))
      (node (ref "J12") (pin "52") (pinfunction "52_52") (pintype "passive"))
      (node (ref "J12") (pin "54") (pinfunction "54_54") (pintype "passive"))
      (node (ref "J12") (pin "56") (pinfunction "56_56") (pintype "passive"))
      (node (ref "J12") (pin "58") (pinfunction "58_58") (pintype "passive"))
      (node (ref "J12") (pin "60") (pinfunction "60_60") (pintype "passive"))
      (node (ref "TVS1") (pin "C") (pinfunction "C_C") (pintype "passive"))
      (node (ref "U6") (pin "B52") (pinfunction "B52_B52") (pintype "passive"))
      (node (ref "U6") (pin "B54") (pinfunction "B54_B54") (pintype "passive"))
      (node (ref "U6") (pin "B56") (pinfunction "B56_B56") (pintype "passive"))
      (node (ref "U6") (pin "B58") (pinfunction "B58_B58") (pintype "passive"))
      (node (ref "U6") (pin "B60") (pinfunction "B60_B60") (pintype "passive"))
    )
    (net (code "84") (name "GND") (class "Default")
      (node (ref "C24") (pin "2") (pinfunction "2_2") (pintype "passive"))
      (node (ref "C25") (pin "1") (pinfunction "1_1") (pintype "passive"))
      (node (ref "C26") (pin "1") (pinfunction "1_1") (pintype "passive"))
      (node (ref "C27") (pin "1") (pinfunction "1_1") (pintype "passive"))
      (node (ref "C28") (pin "1") (pinfunction "1_1") (pintype "passive"))
      (node (ref "C29") (pin "1") (pinfunction "1_1") (pintype "passive"))
      (node (ref "C30") (pin "2") (pinfunction "2_2") (pintype "passive"))
      (node (ref "C31") (pin "1") (pinfunction "1_1") (pintype "passive"))
      (node (ref "C32") (pin "1") (pinfunction "1_1") (pintype "passive"))
      (node (ref "C33") (pin "1") (pinfunction "1_1") (pintype "passive"))
      (node (ref "J12") (pin "11") (pinfunction "11_11") (pintype "passive"))
      (node (ref "J12") (pin "13") (pinfunction "13_13") (pintype "passive"))
      (node (ref "J12") (pin "15") (pinfunction "15_15") (pintype "passive"))
      (node (ref "J12") (pin "17") (pinfunction "17_17") (pintype "passive"))
      (node (ref "J12") (pin "22") (pinfunction "22_22") (pintype "passive"))
      (node (ref "J12") (pin "23") (pinfunction "23_23") (pintype "passive"))
      (node (ref "J12") (pin "24") (pinfunction "24_24") (pintype "passive"))
      (node (ref "J12") (pin "26") (pinfunction "26_26") (pintype "passive"))
      (node (ref "J12") (pin "29") (pinfunction "29_29") (pintype "passive"))
      (node (ref "J12") (pin "31") (pinfunction "31_31") (pintype "passive"))
      (node (ref "J12") (pin "33") (pinfunction "33_33") (pintype "passive"))
      (node (ref "J12") (pin "35") (pinfunction "35_35") (pintype "passive"))
      (node (ref "J12") (pin "37") (pinfunction "37_37") (pintype "passive"))
      (node (ref "J12") (pin "39") (pinfunction "39_39") (pintype "passive"))
      (node (ref "J12") (pin "40") (pinfunction "40_40") (pintype "passive"))
      (node (ref "J12") (pin "41") (pinfunction "41_41") (pintype "passive"))
      (node (ref "J12") (pin "42") (pinfunction "42_42") (pintype "passive"))
      (node (ref "J12") (pin "5") (pinfunction "5_5") (pintype "passive"))
      (node (ref "J13") (pin "1") (pinfunction "1_1") (pintype "passive"))
      (node (ref "J13") (pin "11") (pinfunction "11_11") (pintype "passive"))
      (node (ref "J13") (pin "12") (pinfunction "12_12") (pintype "passive"))
      (node (ref "J13") (pin "2") (pinfunction "2_2") (pintype "passive"))
      (node (ref "J13") (pin "21") (pinfunction "21_21") (pintype "passive"))
      (node (ref "J13") (pin "22") (pinfunction "22_22") (pintype "passive"))
      (node (ref "J13") (pin "31") (pinfunction "31_31") (pintype "passive"))
      (node (ref "J13") (pin "32") (pinfunction "32_32") (pintype "passive"))
      (node (ref "J13") (pin "41") (pinfunction "41_41") (pintype "passive"))
      (node (ref "J13") (pin "42") (pinfunction "42_42") (pintype "passive"))
      (node (ref "J13") (pin "49") (pinfunction "49_49") (pintype "passive"))
      (node (ref "J13") (pin "50") (pinfunction "50_50") (pintype "passive"))
      (node (ref "J13") (pin "55") (pinfunction "55_55") (pintype "passive"))
      (node (ref "J13") (pin "56") (pinfunction "56_56") (pintype "passive"))
      (node (ref "J13") (pin "61") (pinfunction "61_61") (pintype "passive"))
      (node (ref "J13") (pin "62") (pinfunction "62_62") (pintype "passive"))
      (node (ref "J13") (pin "69") (pinfunction "69_69") (pintype "passive"))
      (node (ref "J13") (pin "70") (pinfunction "70_70") (pintype "passive"))
      (node (ref "J14") (pin "SHIELD") (pinfunction "SHIELD_SHIELD") (pintype "passive"))
      (node (ref "J15") (pin "SHIELD") (pinfunction "SHIELD_SHIELD") (pintype "passive"))
      (node (ref "J16") (pin "1") (pinfunction "1_1") (pintype "passive"))
      (node (ref "R22") (pin "2") (pinfunction "2_2") (pintype "passive"))
      (node (ref "R28") (pin "1") (pinfunction "1_1") (pintype "passive"))
      (node (ref "SW1") (pin "2") (pinfunction "2_2") (pintype "passive"))
      (node (ref "TVS1") (pin "A") (pinfunction "A_A") (pintype "passive"))
      (node (ref "TVS3") (pin "C") (pinfunction "C_C") (pintype "passive"))
      (node (ref "TVS4") (pin "3") (pinfunction "GND_3") (pintype "power_in"))
      (node (ref "TVS4") (pin "8") (pinfunction "GND_8") (pintype "power_in"))
      (node (ref "TVS5") (pin "3") (pinfunction "GND_3") (pintype "power_in"))
      (node (ref "TVS5") (pin "8") (pinfunction "GND_8") (pintype "power_in"))
      (node (ref "U5") (pin "1") (pinfunction "PGND_1") (pintype "power_in"))
      (node (ref "U5") (pin "11") (pinfunction "GND_11") (pintype "power_in"))
      (node (ref "U5") (pin "9") (pinfunction "GND_9") (pintype "power_in"))
      (node (ref "U6") (pin "A1") (pinfunction "A1_A1") (pintype "passive"))
      (node (ref "U6") (pin "A11") (pinfunction "A11_A11") (pintype "passive"))
      (node (ref "U6") (pin "A12") (pinfunction "A12_A12") (pintype "passive"))
      (node (ref "U6") (pin "A2") (pinfunction "A2_A2") (pintype "passive"))
      (node (ref "U6") (pin "A21") (pinfunction "A21_A21") (pintype "passive"))
      (node (ref "U6") (pin "A22") (pinfunction "A22_A22") (pintype "passive"))
      (node (ref "U6") (pin "A31") (pinfunction "A31_A31") (pintype "passive"))
      (node (ref "U6") (pin "A32") (pinfunction "A32_A32") (pintype "passive"))
      (node (ref "U6") (pin "A41") (pinfunction "A41_A41") (pintype "passive"))
      (node (ref "U6") (pin "A42") (pinfunction "A42_A42") (pintype "passive"))
      (node (ref "U6") (pin "A49") (pinfunction "A49_A49") (pintype "passive"))
      (node (ref "U6") (pin "A50") (pinfunction "A50_A50") (pintype "passive"))
      (node (ref "U6") (pin "A55") (pinfunction "A55_A55") (pintype "passive"))
      (node (ref "U6") (pin "A56") (pinfunction "A56_A56") (pintype "passive"))
      (node (ref "U6") (pin "A61") (pinfunction "A61_A61") (pintype "passive"))
      (node (ref "U6") (pin "A62") (pinfunction "A62_A62") (pintype "passive"))
      (node (ref "U6") (pin "A69") (pinfunction "A69_A69") (pintype "passive"))
      (node (ref "U6") (pin "A70") (pinfunction "A70_A70") (pintype "passive"))
      (node (ref "U6") (pin "B11") (pinfunction "B11_B11") (pintype "passive"))
      (node (ref "U6") (pin "B13") (pinfunction "B13_B13") (pintype "passive"))
      (node (ref "U6") (pin "B15") (pinfunction "B15_B15") (pintype "passive"))
      (node (ref "U6") (pin "B17") (pinfunction "B17_B17") (pintype "passive"))
      (node (ref "U6") (pin "B22") (pinfunction "B22_B22") (pintype "passive"))
      (node (ref "U6") (pin "B23") (pinfunction "B23_B23") (pintype "passive"))
      (node (ref "U6") (pin "B24") (pinfunction "B24_B24") (pintype "passive"))
      (node (ref "U6") (pin "B26") (pinfunction "B26_B26") (pintype "passive"))
      (node (ref "U6") (pin "B29") (pinfunction "B29_B29") (pintype "passive"))
      (node (ref "U6") (pin "B31") (pinfunction "B31_B31") (pintype "passive"))
      (node (ref "U6") (pin "B33") (pinfunction "B33_B33") (pintype "passive"))
      (node (ref "U6") (pin "B35") (pinfunction "B35_B35") (pintype "passive"))
      (node (ref "U6") (pin "B37") (pinfunction "B37_B37") (pintype "passive"))
      (node (ref "U6") (pin "B39") (pinfunction "B39_B39") (pintype "passive"))
      (node (ref "U6") (pin "B40") (pinfunction "B40_B40") (pintype "passive"))
      (node (ref "U6") (pin "B41") (pinfunction "B41_B41") (pintype "passive"))
      (node (ref "U6") (pin "B42") (pinfunction "B42_B42") (pintype "passive"))
      (node (ref "U6") (pin "B5") (pinfunction "B5_B5") (pintype "passive"))
      (node (ref "U8") (pin "4") (pinfunction "GND_4") (pintype "power_in"))
    )
    (net (code "85") (name "Net-(C29-Pad2)") (class "Default")
      (node (ref "C29") (pin "2") (pinfunction "2_2") (pintype "passive"))
      (node (ref "FB3") (pin "1") (pinfunction "1_1") (pintype "passive"))
      (node (ref "L1") (pin "2") (pinfunction "2_2") (pintype "passive"))
      (node (ref "R21") (pin "2") (pinfunction "2_2") (pintype "passive"))
    )
    (net (code "86") (name "Net-(C33-Pad2)") (class "Default")
      (node (ref "C33") (pin "2") (pinfunction "2_2") (pintype "passive"))
      (node (ref "R27") (pin "1") (pinfunction "1_1") (pintype "passive"))
    )
    (net (code "87") (name "Net-(J12-Pad2)") (class "Default")
      (node (ref "J12") (pin "2") (pinfunction "2_2") (pintype "passive"))
      (node (ref "U6") (pin "B2") (pinfunction "B2_B2") (pintype "passive"))
    )
    (net (code "88") (name "Net-(J12-Pad6)") (class "Default")
      (node (ref "J12") (pin "6") (pinfunction "6_6") (pintype "passive"))
      (node (ref "U6") (pin "B6") (pinfunction "B6_B6") (pintype "passive"))
    )
    (net (code "89") (name "Net-(J14-GREEN_C)") (class "Default")
      (node (ref "J14") (pin "L2") (pinfunction "GREEN_C_L2") (pintype "passive"))
      (node (ref "R23") (pin "2") (pinfunction "2_2") (pintype "passive"))
    )
    (net (code "90") (name "Net-(J14-YELLOW_C)") (class "Default")
      (node (ref "J14") (pin "L4") (pinfunction "YELLOW_C_L4") (pintype "passive"))
      (node (ref "R24") (pin "2") (pinfunction "2_2") (pintype "passive"))
    )
    (net (code "91") (name "Net-(J15-GREEN_C)") (class "Default")
      (node (ref "J15") (pin "L2") (pinfunction "GREEN_C_L2") (pintype "passive"))
      (node (ref "R25") (pin "2") (pinfunction "2_2") (pintype "passive"))
    )
    (net (code "92") (name "Net-(J15-YELLOW_C)") (class "Default")
      (node (ref "J15") (pin "L4") (pinfunction "YELLOW_C_L4") (pintype "passive"))
      (node (ref "R26") (pin "2") (pinfunction "2_2") (pintype "passive"))
    )
    (net (code "93") (name "Net-(U5-EN{slash}UVLO)") (class "Default")
      (node (ref "R19") (pin "1") (pinfunction "1_1") (pintype "passive"))
      (node (ref "R22") (pin "1") (pinfunction "1_1") (pintype "passive"))
      (node (ref "U5") (pin "3") (pinfunction "EN/UVLO_3") (pintype "input"))
    )
    (net (code "94") (name "Net-(U5-FB{slash}VO)") (class "Default")
      (node (ref "R21") (pin "1") (pinfunction "1_1") (pintype "passive"))
      (node (ref "R28") (pin "2") (pinfunction "2_2") (pintype "passive"))
      (node (ref "U5") (pin "5") (pinfunction "FB/VO_5") (pintype "input"))
    )
    (net (code "95") (name "Net-(U5-LX)") (class "Default")
      (node (ref "L1") (pin "1") (pinfunction "1_1") (pintype "passive"))
      (node (ref "U5") (pin "10") (pinfunction "LX_10") (pintype "output"))
    )
    (net (code "96") (name "Net-(U5-NC{slash}COMP)") (class "Default")
      (node (ref "C32") (pin "2") (pinfunction "2_2") (pintype "passive"))
      (node (ref "R27") (pin "2") (pinfunction "2_2") (pintype "passive"))
      (node (ref "U5") (pin "7") (pinfunction "NC/COMP_7") (pintype "input"))
    )
    (net (code "97") (name "Net-(U5-SS)") (class "Default")
      (node (ref "C31") (pin "2") (pinfunction "2_2") (pintype "passive"))
      (node (ref "U5") (pin "6") (pinfunction "SS_6") (pintype "input"))
    )
    (net (code "98") (name "Net-(U5-VCC)") (class "Default")
      (node (ref "C30") (pin "1") (pinfunction "1_1") (pintype "passive"))
      (node (ref "U5") (pin "4") (pinfunction "VCC_4") (pintype "power_in"))
    )
    (net (code "99") (name "Net-(U7-IOUT)") (class "Default")
      (node (ref "U7") (pin "2") (pinfunction "IOUT_2") (pintype "passive"))
      (node (ref "U8") (pin "1") (pinfunction "ANODE_1") (pintype "passive"))
    )
    (net (code "100") (name "Net-(U7-REXT)") (class "Default")
      (node (ref "R18") (pin "1") (pinfunction "1_1") (pintype "passive"))
      (node (ref "U7") (pin "4") (pinfunction "REXT_4") (pintype "passive"))
    )
    (net (code "101") (name "Net-(U7-VS)") (class "Default")
      (node (ref "D2") (pin "C") (pinfunction "C_C") (pintype "passive"))
      (node (ref "R18") (pin "2") (pinfunction "2_2") (pintype "passive"))
      (node (ref "U7") (pin "5") (pinfunction "VS_5") (pintype "passive"))
    )
    (net (code "102") (name "VBUS") (class "Default")
      (node (ref "C27") (pin "2") (pinfunction "2_2") (pintype "passive"))
      (node (ref "C28") (pin "2") (pinfunction "2_2") (pintype "passive"))
      (node (ref "D1") (pin "C") (pinfunction "C_C") (pintype "passive"))
      (node (ref "J12") (pin "4") (pinfunction "4_4") (pintype "passive"))
      (node (ref "R19") (pin "2") (pinfunction "2_2") (pintype "passive"))
      (node (ref "U5") (pin "2") (pinfunction "VIN_2") (pintype "power_in"))
      (node (ref "U6") (pin "B4") (pinfunction "B4_B4") (pintype "passive"))
    )
    (net (code "103") (name "VDDA") (class "Default")
      (node (ref "J13") (pin "64") (pinfunction "64_64") (pintype "passive"))
      (node (ref "U6") (pin "A64") (pinfunction "A64_A64") (pintype "passive"))
    )
    (net (code "104") (name "V_IN") (class "Default")
      (node (ref "D1") (pin "A") (pinfunction "A_A") (pintype "passive"))
      (node (ref "J16") (pin "2") (pinfunction "2_2") (pintype "passive"))
      (node (ref "TVS3") (pin "A") (pinfunction "A_A") (pintype "passive"))
    )
    (net (code "105") (name "V_REF") (class "Default")
      (node (ref "J13") (pin "66") (pinfunction "66_66") (pintype "passive"))
      (node (ref "U6") (pin "A66") (pinfunction "A66_A66") (pintype "passive"))
    )
    (net (code "106") (name "unconnected-(J14-VC1+-Pad7)") (class "Default")
      (node (ref "J14") (pin "7") (pinfunction "VC1+_7") (pintype "passive"))
    )
    (net (code "107") (name "unconnected-(J14-VC1--Pad2)") (class "Default")
      (node (ref "J14") (pin "2") (pinfunction "VC1-_2") (pintype "passive"))
    )
    (net (code "108") (name "unconnected-(J15-VC1+-Pad7)") (class "Default")
      (node (ref "J15") (pin "7") (pinfunction "VC1+_7") (pintype "passive"))
    )
    (net (code "109") (name "unconnected-(J15-VC1--Pad2)") (class "Default")
      (node (ref "J15") (pin "2") (pinfunction "VC1-_2") (pintype "passive"))
    )
    (net (code "110") (name "unconnected-(ST1-Pad1)") (class "Default")
      (node (ref "ST1") (pin "1") (pinfunction "1_1") (pintype "passive"))
    )
    (net (code "111") (name "unconnected-(ST2-Pad1)") (class "Default")
      (node (ref "ST2") (pin "1") (pinfunction "1_1") (pintype "passive"))
    )
    (net (code "112") (name "unconnected-(ST3-Pad1)") (class "Default")
      (node (ref "ST3") (pin "1") (pinfunction "1_1") (pintype "passive"))
    )
    (net (code "113") (name "unconnected-(ST4-Pad1)") (class "Default")
      (node (ref "ST4") (pin "1") (pinfunction "1_1") (pintype "passive"))
    )
    (net (code "114") (name "unconnected-(U5-RESET-Pad8)") (class "Default")
      (node (ref "U5") (pin "8") (pinfunction "RESET_8") (pintype "open_collector"))
    )
    (net (code "115") (name "unconnected-(U7-NC-Pad1)") (class "Default")
      (node (ref "U7") (pin "1") (pinfunction "NC_1") (pintype "passive"))
    )
  )
)
